# W051D.net
KiCad netlist of a schematic drawn in EAGLE
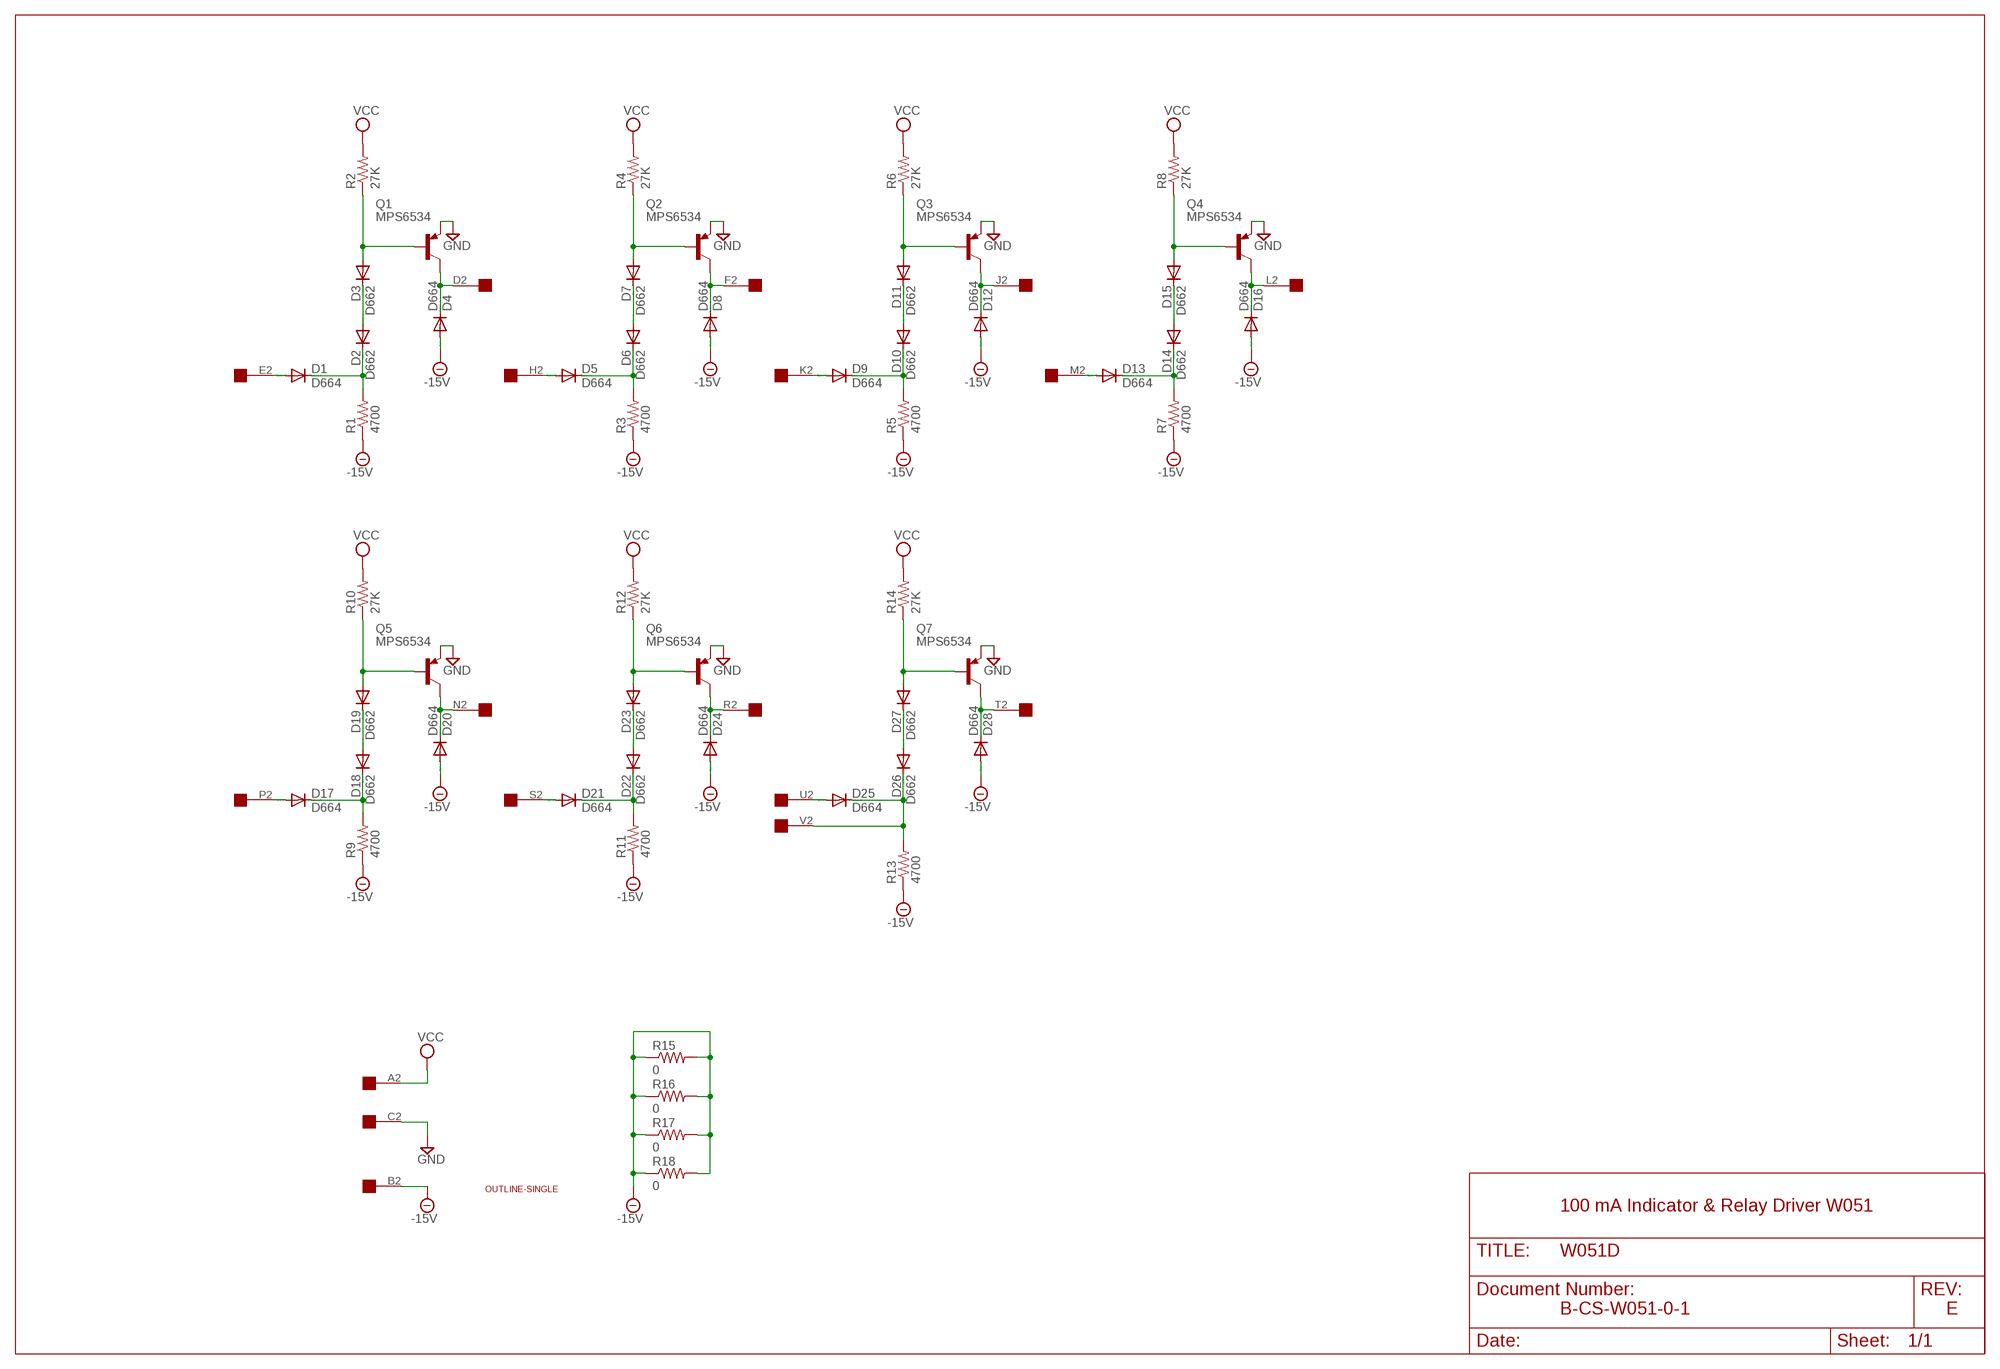
[diagram p0: schematic, sheet 1]

(export (version "E")
  (design (tool "Eeschema 10.0.6"))
  (components
    (comp (ref "D1")
      (value "D664")
      (footprint "eagle-import:DO35-10")
      (libsource (lib "eagle-import") (part "DIODE-DO35-10"))
    )
    (comp (ref "D2")
      (value "D662")
      (footprint "eagle-import:DO35-10")
      (libsource (lib "eagle-import") (part "DIODE-DO35-10"))
    )
    (comp (ref "D3")
      (value "D662")
      (footprint "eagle-import:DO35-10")
      (libsource (lib "eagle-import") (part "DIODE-DO35-10"))
    )
    (comp (ref "D4")
      (value "D664")
      (footprint "eagle-import:DO35-10")
      (libsource (lib "eagle-import") (part "DIODE-DO35-10"))
    )
    (comp (ref "D5")
      (value "D664")
      (footprint "eagle-import:DO35-10")
      (libsource (lib "eagle-import") (part "DIODE-DO35-10"))
    )
    (comp (ref "D6")
      (value "D662")
      (footprint "eagle-import:DO35-10")
      (libsource (lib "eagle-import") (part "DIODE-DO35-10"))
    )
    (comp (ref "D7")
      (value "D662")
      (footprint "eagle-import:DO35-10")
      (libsource (lib "eagle-import") (part "DIODE-DO35-10"))
    )
    (comp (ref "D8")
      (value "D664")
      (footprint "eagle-import:DO35-10")
      (libsource (lib "eagle-import") (part "DIODE-DO35-10"))
    )
    (comp (ref "D9")
      (value "D664")
      (footprint "eagle-import:DO35-10")
      (libsource (lib "eagle-import") (part "DIODE-DO35-10"))
    )
    (comp (ref "D10")
      (value "D662")
      (footprint "eagle-import:DO35-10")
      (libsource (lib "eagle-import") (part "DIODE-DO35-10"))
    )
    (comp (ref "D11")
      (value "D662")
      (footprint "eagle-import:DO35-10")
      (libsource (lib "eagle-import") (part "DIODE-DO35-10"))
    )
    (comp (ref "D12")
      (value "D664")
      (footprint "eagle-import:DO35-10")
      (libsource (lib "eagle-import") (part "DIODE-DO35-10"))
    )
    (comp (ref "D13")
      (value "D664")
      (footprint "eagle-import:DO35-10")
      (libsource (lib "eagle-import") (part "DIODE-DO35-10"))
    )
    (comp (ref "D14")
      (value "D662")
      (footprint "eagle-import:DO35-10")
      (libsource (lib "eagle-import") (part "DIODE-DO35-10"))
    )
    (comp (ref "D15")
      (value "D662")
      (footprint "eagle-import:DO35-10")
      (libsource (lib "eagle-import") (part "DIODE-DO35-10"))
    )
    (comp (ref "D16")
      (value "D664")
      (footprint "eagle-import:DO35-10")
      (libsource (lib "eagle-import") (part "DIODE-DO35-10"))
    )
    (comp (ref "D17")
      (value "D664")
      (footprint "eagle-import:DO35-10")
      (libsource (lib "eagle-import") (part "DIODE-DO35-10"))
    )
    (comp (ref "D18")
      (value "D662")
      (footprint "eagle-import:DO35-10")
      (libsource (lib "eagle-import") (part "DIODE-DO35-10"))
    )
    (comp (ref "D19")
      (value "D662")
      (footprint "eagle-import:DO35-10")
      (libsource (lib "eagle-import") (part "DIODE-DO35-10"))
    )
    (comp (ref "D20")
      (value "D664")
      (footprint "eagle-import:DO35-10")
      (libsource (lib "eagle-import") (part "DIODE-DO35-10"))
    )
    (comp (ref "D21")
      (value "D664")
      (footprint "eagle-import:DO35-10")
      (libsource (lib "eagle-import") (part "DIODE-DO35-10"))
    )
    (comp (ref "D22")
      (value "D662")
      (footprint "eagle-import:DO35-10")
      (libsource (lib "eagle-import") (part "DIODE-DO35-10"))
    )
    (comp (ref "D23")
      (value "D662")
      (footprint "eagle-import:DO35-10")
      (libsource (lib "eagle-import") (part "DIODE-DO35-10"))
    )
    (comp (ref "D24")
      (value "D664")
      (footprint "eagle-import:DO35-10")
      (libsource (lib "eagle-import") (part "DIODE-DO35-10"))
    )
    (comp (ref "D25")
      (value "D664")
      (footprint "eagle-import:DO35-10")
      (libsource (lib "eagle-import") (part "DIODE-DO35-10"))
    )
    (comp (ref "D26")
      (value "D662")
      (footprint "eagle-import:DO35-10")
      (libsource (lib "eagle-import") (part "DIODE-DO35-10"))
    )
    (comp (ref "D27")
      (value "D662")
      (footprint "eagle-import:DO35-10")
      (libsource (lib "eagle-import") (part "DIODE-DO35-10"))
    )
    (comp (ref "D28")
      (value "D664")
      (footprint "eagle-import:DO35-10")
      (libsource (lib "eagle-import") (part "DIODE-DO35-10"))
    )
    (comp (ref "Q1")
      (value "MPS6534")
      (footprint "eagle-import:TO5")
      (libsource (lib "eagle-import") (part "-PNP-TO5"))
    )
    (comp (ref "Q2")
      (value "MPS6534")
      (footprint "eagle-import:TO5")
      (libsource (lib "eagle-import") (part "-PNP-TO5"))
    )
    (comp (ref "Q3")
      (value "MPS6534")
      (footprint "eagle-import:TO5")
      (libsource (lib "eagle-import") (part "-PNP-TO5"))
    )
    (comp (ref "Q4")
      (value "MPS6534")
      (footprint "eagle-import:TO5")
      (libsource (lib "eagle-import") (part "-PNP-TO5"))
    )
    (comp (ref "Q5")
      (value "MPS6534")
      (footprint "eagle-import:TO5")
      (libsource (lib "eagle-import") (part "-PNP-TO5"))
    )
    (comp (ref "Q6")
      (value "MPS6534")
      (footprint "eagle-import:TO5")
      (libsource (lib "eagle-import") (part "-PNP-TO5"))
    )
    (comp (ref "Q7")
      (value "MPS6534")
      (footprint "eagle-import:TO5")
      (libsource (lib "eagle-import") (part "-PNP-TO5"))
    )
    (comp (ref "R1")
      (value "4700")
      (footprint "eagle-import:0207_10")
      (libsource (lib "eagle-import") (part "R-US_0207/10"))
    )
    (comp (ref "R2")
      (value "27K")
      (footprint "eagle-import:0207_10")
      (libsource (lib "eagle-import") (part "R-US_0207/10"))
    )
    (comp (ref "R3")
      (value "4700")
      (footprint "eagle-import:0207_10")
      (libsource (lib "eagle-import") (part "R-US_0207/10"))
    )
    (comp (ref "R4")
      (value "27K")
      (footprint "eagle-import:0207_10")
      (libsource (lib "eagle-import") (part "R-US_0207/10"))
    )
    (comp (ref "R5")
      (value "4700")
      (footprint "eagle-import:0207_10")
      (libsource (lib "eagle-import") (part "R-US_0207/10"))
    )
    (comp (ref "R6")
      (value "27K")
      (footprint "eagle-import:0207_10")
      (libsource (lib "eagle-import") (part "R-US_0207/10"))
    )
    (comp (ref "R7")
      (value "4700")
      (footprint "eagle-import:0207_10")
      (libsource (lib "eagle-import") (part "R-US_0207/10"))
    )
    (comp (ref "R8")
      (value "27K")
      (footprint "eagle-import:0207_10")
      (libsource (lib "eagle-import") (part "R-US_0207/10"))
    )
    (comp (ref "R9")
      (value "4700")
      (footprint "eagle-import:0207_10")
      (libsource (lib "eagle-import") (part "R-US_0207/10"))
    )
    (comp (ref "R10")
      (value "27K")
      (footprint "eagle-import:0207_10")
      (libsource (lib "eagle-import") (part "R-US_0207/10"))
    )
    (comp (ref "R11")
      (value "4700")
      (footprint "eagle-import:0207_10")
      (libsource (lib "eagle-import") (part "R-US_0207/10"))
    )
    (comp (ref "R12")
      (value "27K")
      (footprint "eagle-import:0207_10")
      (libsource (lib "eagle-import") (part "R-US_0207/10"))
    )
    (comp (ref "R13")
      (value "4700")
      (footprint "eagle-import:0207_10")
      (libsource (lib "eagle-import") (part "R-US_0207/10"))
    )
    (comp (ref "R14")
      (value "27K")
      (footprint "eagle-import:0207_10")
      (libsource (lib "eagle-import") (part "R-US_0207/10"))
    )
    (comp (ref "R15")
      (value "0")
      (footprint "eagle-import:0207_10")
      (libsource (lib "eagle-import") (part "R-US_0207/10"))
    )
    (comp (ref "R16")
      (value "0")
      (footprint "eagle-import:0207_10")
      (libsource (lib "eagle-import") (part "R-US_0207/10"))
    )
    (comp (ref "R17")
      (value "0")
      (footprint "eagle-import:0207_10")
      (libsource (lib "eagle-import") (part "R-US_0207/10"))
    )
    (comp (ref "R18")
      (value "0")
      (footprint "eagle-import:0207_10")
      (libsource (lib "eagle-import") (part "R-US_0207/10"))
    )
    (comp (ref "U$1")
      (value "OUTLINE-SINGLE")
      (footprint "eagle-import:SINGLE")
      (libsource (lib "eagle-import") (part "OUTLINE-SINGLE"))
    )
    (comp (ref "U$2")
      (value "EDGE-1")
      (footprint "eagle-import:EDGE-CON1")
      (libsource (lib "eagle-import") (part "EDGE-1"))
    )
  )
  (nets
    (net (code "1") (name "-15V") (class "Default")
      (node (ref "D12") (pin "A") (pinfunction "A_A") (pintype "passive"))
      (node (ref "D16") (pin "A") (pinfunction "A_A") (pintype "passive"))
      (node (ref "D20") (pin "A") (pinfunction "A_A") (pintype "passive"))
      (node (ref "D24") (pin "A") (pinfunction "A_A") (pintype "passive"))
      (node (ref "D28") (pin "A") (pinfunction "A_A") (pintype "passive"))
      (node (ref "D4") (pin "A") (pinfunction "A_A") (pintype "passive"))
      (node (ref "D8") (pin "A") (pinfunction "A_A") (pintype "passive"))
      (node (ref "R1") (pin "1") (pinfunction "1_1") (pintype "passive"))
      (node (ref "R11") (pin "1") (pinfunction "1_1") (pintype "passive"))
      (node (ref "R13") (pin "1") (pinfunction "1_1") (pintype "passive"))
      (node (ref "R15") (pin "1") (pinfunction "1_1") (pintype "passive"))
      (node (ref "R15") (pin "2") (pinfunction "2_2") (pintype "passive"))
      (node (ref "R16") (pin "1") (pinfunction "1_1") (pintype "passive"))
      (node (ref "R16") (pin "2") (pinfunction "2_2") (pintype "passive"))
      (node (ref "R17") (pin "1") (pinfunction "1_1") (pintype "passive"))
      (node (ref "R17") (pin "2") (pinfunction "2_2") (pintype "passive"))
      (node (ref "R18") (pin "1") (pinfunction "1_1") (pintype "passive"))
      (node (ref "R18") (pin "2") (pinfunction "2_2") (pintype "passive"))
      (node (ref "R3") (pin "1") (pinfunction "1_1") (pintype "passive"))
      (node (ref "R5") (pin "1") (pinfunction "1_1") (pintype "passive"))
      (node (ref "R7") (pin "1") (pinfunction "1_1") (pintype "passive"))
      (node (ref "R9") (pin "1") (pinfunction "1_1") (pintype "passive"))
      (node (ref "U$2") (pin "B2") (pinfunction "1_B2") (pintype "bidirectional"))
    )
    (net (code "2") (name "GND") (class "Default")
      (node (ref "Q1") (pin "1") (pinfunction "E_1") (pintype "passive"))
      (node (ref "Q2") (pin "1") (pinfunction "E_1") (pintype "passive"))
      (node (ref "Q3") (pin "1") (pinfunction "E_1") (pintype "passive"))
      (node (ref "Q4") (pin "1") (pinfunction "E_1") (pintype "passive"))
      (node (ref "Q5") (pin "1") (pinfunction "E_1") (pintype "passive"))
      (node (ref "Q6") (pin "1") (pinfunction "E_1") (pintype "passive"))
      (node (ref "Q7") (pin "1") (pinfunction "E_1") (pintype "passive"))
      (node (ref "U$2") (pin "C2") (pinfunction "1_C2") (pintype "bidirectional"))
    )
    (net (code "3") (name "Net-(D1-PadC)") (class "Default")
      (node (ref "D1") (pin "C") (pinfunction "C_C") (pintype "passive"))
      (node (ref "D2") (pin "C") (pinfunction "C_C") (pintype "passive"))
      (node (ref "R1") (pin "2") (pinfunction "2_2") (pintype "passive"))
    )
    (net (code "4") (name "Net-(D2-PadA)") (class "Default")
      (node (ref "D2") (pin "A") (pinfunction "A_A") (pintype "passive"))
      (node (ref "D3") (pin "C") (pinfunction "C_C") (pintype "passive"))
    )
    (net (code "5") (name "Net-(D5-PadC)") (class "Default")
      (node (ref "D5") (pin "C") (pinfunction "C_C") (pintype "passive"))
      (node (ref "D6") (pin "C") (pinfunction "C_C") (pintype "passive"))
      (node (ref "R3") (pin "2") (pinfunction "2_2") (pintype "passive"))
    )
    (net (code "6") (name "Net-(D6-PadA)") (class "Default")
      (node (ref "D6") (pin "A") (pinfunction "A_A") (pintype "passive"))
      (node (ref "D7") (pin "C") (pinfunction "C_C") (pintype "passive"))
    )
    (net (code "7") (name "Net-(D10-PadA)") (class "Default")
      (node (ref "D10") (pin "A") (pinfunction "A_A") (pintype "passive"))
      (node (ref "D11") (pin "C") (pinfunction "C_C") (pintype "passive"))
    )
    (net (code "8") (name "Net-(D10-PadC)") (class "Default")
      (node (ref "D10") (pin "C") (pinfunction "C_C") (pintype "passive"))
      (node (ref "D9") (pin "C") (pinfunction "C_C") (pintype "passive"))
      (node (ref "R5") (pin "2") (pinfunction "2_2") (pintype "passive"))
    )
    (net (code "9") (name "Net-(D13-PadC)") (class "Default")
      (node (ref "D13") (pin "C") (pinfunction "C_C") (pintype "passive"))
      (node (ref "D14") (pin "C") (pinfunction "C_C") (pintype "passive"))
      (node (ref "R7") (pin "2") (pinfunction "2_2") (pintype "passive"))
    )
    (net (code "10") (name "Net-(D14-PadA)") (class "Default")
      (node (ref "D14") (pin "A") (pinfunction "A_A") (pintype "passive"))
      (node (ref "D15") (pin "C") (pinfunction "C_C") (pintype "passive"))
    )
    (net (code "11") (name "Net-(D17-PadC)") (class "Default")
      (node (ref "D17") (pin "C") (pinfunction "C_C") (pintype "passive"))
      (node (ref "D18") (pin "C") (pinfunction "C_C") (pintype "passive"))
      (node (ref "R9") (pin "2") (pinfunction "2_2") (pintype "passive"))
    )
    (net (code "12") (name "Net-(D18-PadA)") (class "Default")
      (node (ref "D18") (pin "A") (pinfunction "A_A") (pintype "passive"))
      (node (ref "D19") (pin "C") (pinfunction "C_C") (pintype "passive"))
    )
    (net (code "13") (name "Net-(D21-PadC)") (class "Default")
      (node (ref "D21") (pin "C") (pinfunction "C_C") (pintype "passive"))
      (node (ref "D22") (pin "C") (pinfunction "C_C") (pintype "passive"))
      (node (ref "R11") (pin "2") (pinfunction "2_2") (pintype "passive"))
    )
    (net (code "14") (name "Net-(D22-PadA)") (class "Default")
      (node (ref "D22") (pin "A") (pinfunction "A_A") (pintype "passive"))
      (node (ref "D23") (pin "C") (pinfunction "C_C") (pintype "passive"))
    )
    (net (code "15") (name "Net-(D26-PadA)") (class "Default")
      (node (ref "D26") (pin "A") (pinfunction "A_A") (pintype "passive"))
      (node (ref "D27") (pin "C") (pinfunction "C_C") (pintype "passive"))
    )
    (net (code "16") (name "Net-(Q1-B)") (class "Default")
      (node (ref "D3") (pin "A") (pinfunction "A_A") (pintype "passive"))
      (node (ref "Q1") (pin "2") (pinfunction "B_2") (pintype "passive"))
      (node (ref "R2") (pin "1") (pinfunction "1_1") (pintype "passive"))
    )
    (net (code "17") (name "Net-(Q1-C)") (class "Default")
      (node (ref "D4") (pin "C") (pinfunction "C_C") (pintype "passive"))
      (node (ref "Q1") (pin "3") (pinfunction "C_3") (pintype "passive"))
      (node (ref "U$2") (pin "D2") (pinfunction "1_D2") (pintype "bidirectional"))
    )
    (net (code "18") (name "Net-(Q2-B)") (class "Default")
      (node (ref "D7") (pin "A") (pinfunction "A_A") (pintype "passive"))
      (node (ref "Q2") (pin "2") (pinfunction "B_2") (pintype "passive"))
      (node (ref "R4") (pin "1") (pinfunction "1_1") (pintype "passive"))
    )
    (net (code "19") (name "Net-(Q2-C)") (class "Default")
      (node (ref "D8") (pin "C") (pinfunction "C_C") (pintype "passive"))
      (node (ref "Q2") (pin "3") (pinfunction "C_3") (pintype "passive"))
      (node (ref "U$2") (pin "F2") (pinfunction "1_F2") (pintype "bidirectional"))
    )
    (net (code "20") (name "Net-(Q3-B)") (class "Default")
      (node (ref "D11") (pin "A") (pinfunction "A_A") (pintype "passive"))
      (node (ref "Q3") (pin "2") (pinfunction "B_2") (pintype "passive"))
      (node (ref "R6") (pin "1") (pinfunction "1_1") (pintype "passive"))
    )
    (net (code "21") (name "Net-(Q3-C)") (class "Default")
      (node (ref "D12") (pin "C") (pinfunction "C_C") (pintype "passive"))
      (node (ref "Q3") (pin "3") (pinfunction "C_3") (pintype "passive"))
      (node (ref "U$2") (pin "J2") (pinfunction "1_J2") (pintype "bidirectional"))
    )
    (net (code "22") (name "Net-(Q4-B)") (class "Default")
      (node (ref "D15") (pin "A") (pinfunction "A_A") (pintype "passive"))
      (node (ref "Q4") (pin "2") (pinfunction "B_2") (pintype "passive"))
      (node (ref "R8") (pin "1") (pinfunction "1_1") (pintype "passive"))
    )
    (net (code "23") (name "Net-(Q4-C)") (class "Default")
      (node (ref "D16") (pin "C") (pinfunction "C_C") (pintype "passive"))
      (node (ref "Q4") (pin "3") (pinfunction "C_3") (pintype "passive"))
      (node (ref "U$2") (pin "L2") (pinfunction "1_L2") (pintype "bidirectional"))
    )
    (net (code "24") (name "Net-(Q5-B)") (class "Default")
      (node (ref "D19") (pin "A") (pinfunction "A_A") (pintype "passive"))
      (node (ref "Q5") (pin "2") (pinfunction "B_2") (pintype "passive"))
      (node (ref "R10") (pin "1") (pinfunction "1_1") (pintype "passive"))
    )
    (net (code "25") (name "Net-(Q5-C)") (class "Default")
      (node (ref "D20") (pin "C") (pinfunction "C_C") (pintype "passive"))
      (node (ref "Q5") (pin "3") (pinfunction "C_3") (pintype "passive"))
      (node (ref "U$2") (pin "N2") (pinfunction "1_N2") (pintype "bidirectional"))
    )
    (net (code "26") (name "Net-(Q6-B)") (class "Default")
      (node (ref "D23") (pin "A") (pinfunction "A_A") (pintype "passive"))
      (node (ref "Q6") (pin "2") (pinfunction "B_2") (pintype "passive"))
      (node (ref "R12") (pin "1") (pinfunction "1_1") (pintype "passive"))
    )
    (net (code "27") (name "Net-(Q6-C)") (class "Default")
      (node (ref "D24") (pin "C") (pinfunction "C_C") (pintype "passive"))
      (node (ref "Q6") (pin "3") (pinfunction "C_3") (pintype "passive"))
      (node (ref "U$2") (pin "R2") (pinfunction "1_R2") (pintype "bidirectional"))
    )
    (net (code "28") (name "Net-(Q7-B)") (class "Default")
      (node (ref "D27") (pin "A") (pinfunction "A_A") (pintype "passive"))
      (node (ref "Q7") (pin "2") (pinfunction "B_2") (pintype "passive"))
      (node (ref "R14") (pin "1") (pinfunction "1_1") (pintype "passive"))
    )
    (net (code "29") (name "Net-(Q7-C)") (class "Default")
      (node (ref "D28") (pin "C") (pinfunction "C_C") (pintype "passive"))
      (node (ref "Q7") (pin "3") (pinfunction "C_3") (pintype "passive"))
      (node (ref "U$2") (pin "T2") (pinfunction "1_T2") (pintype "bidirectional"))
    )
    (net (code "30") (name "Net-(U$2E-1)") (class "Default")
      (node (ref "D1") (pin "A") (pinfunction "A_A") (pintype "passive"))
      (node (ref "U$2") (pin "E2") (pinfunction "1_E2") (pintype "bidirectional"))
    )
    (net (code "31") (name "Net-(U$2G-1)") (class "Default")
      (node (ref "D5") (pin "A") (pinfunction "A_A") (pintype "passive"))
      (node (ref "U$2") (pin "H2") (pinfunction "1_H2") (pintype "bidirectional"))
    )
    (net (code "32") (name "Net-(U$2I-1)") (class "Default")
      (node (ref "D9") (pin "A") (pinfunction "A_A") (pintype "passive"))
      (node (ref "U$2") (pin "K2") (pinfunction "1_K2") (pintype "bidirectional"))
    )
    (net (code "33") (name "Net-(U$2K-1)") (class "Default")
      (node (ref "D13") (pin "A") (pinfunction "A_A") (pintype "passive"))
      (node (ref "U$2") (pin "M2") (pinfunction "1_M2") (pintype "bidirectional"))
    )
    (net (code "34") (name "Net-(U$2M-1)") (class "Default")
      (node (ref "D17") (pin "A") (pinfunction "A_A") (pintype "passive"))
      (node (ref "U$2") (pin "P2") (pinfunction "1_P2") (pintype "bidirectional"))
    )
    (net (code "35") (name "Net-(U$2O-1)") (class "Default")
      (node (ref "D21") (pin "A") (pinfunction "A_A") (pintype "passive"))
      (node (ref "U$2") (pin "S2") (pinfunction "1_S2") (pintype "bidirectional"))
    )
    (net (code "36") (name "Net-(U$2Q-1)") (class "Default")
      (node (ref "D25") (pin "A") (pinfunction "A_A") (pintype "passive"))
      (node (ref "U$2") (pin "U2") (pinfunction "1_U2") (pintype "bidirectional"))
    )
    (net (code "37") (name "Net-(U$2R-1)") (class "Default")
      (node (ref "D25") (pin "C") (pinfunction "C_C") (pintype "passive"))
      (node (ref "D26") (pin "C") (pinfunction "C_C") (pintype "passive"))
      (node (ref "R13") (pin "2") (pinfunction "2_2") (pintype "passive"))
      (node (ref "U$2") (pin "V2") (pinfunction "1_V2") (pintype "bidirectional"))
    )
    (net (code "38") (name "VCC") (class "Default")
      (node (ref "R10") (pin "2") (pinfunction "2_2") (pintype "passive"))
      (node (ref "R12") (pin "2") (pinfunction "2_2") (pintype "passive"))
      (node (ref "R14") (pin "2") (pinfunction "2_2") (pintype "passive"))
      (node (ref "R2") (pin "2") (pinfunction "2_2") (pintype "passive"))
      (node (ref "R4") (pin "2") (pinfunction "2_2") (pintype "passive"))
      (node (ref "R6") (pin "2") (pinfunction "2_2") (pintype "passive"))
      (node (ref "R8") (pin "2") (pinfunction "2_2") (pintype "passive"))
      (node (ref "U$2") (pin "A2") (pinfunction "1_A2") (pintype "bidirectional"))
    )
  )
)
